# Noninvasive_Nexmeter.net
KiCad netlist of a schematic drawn in EAGLE
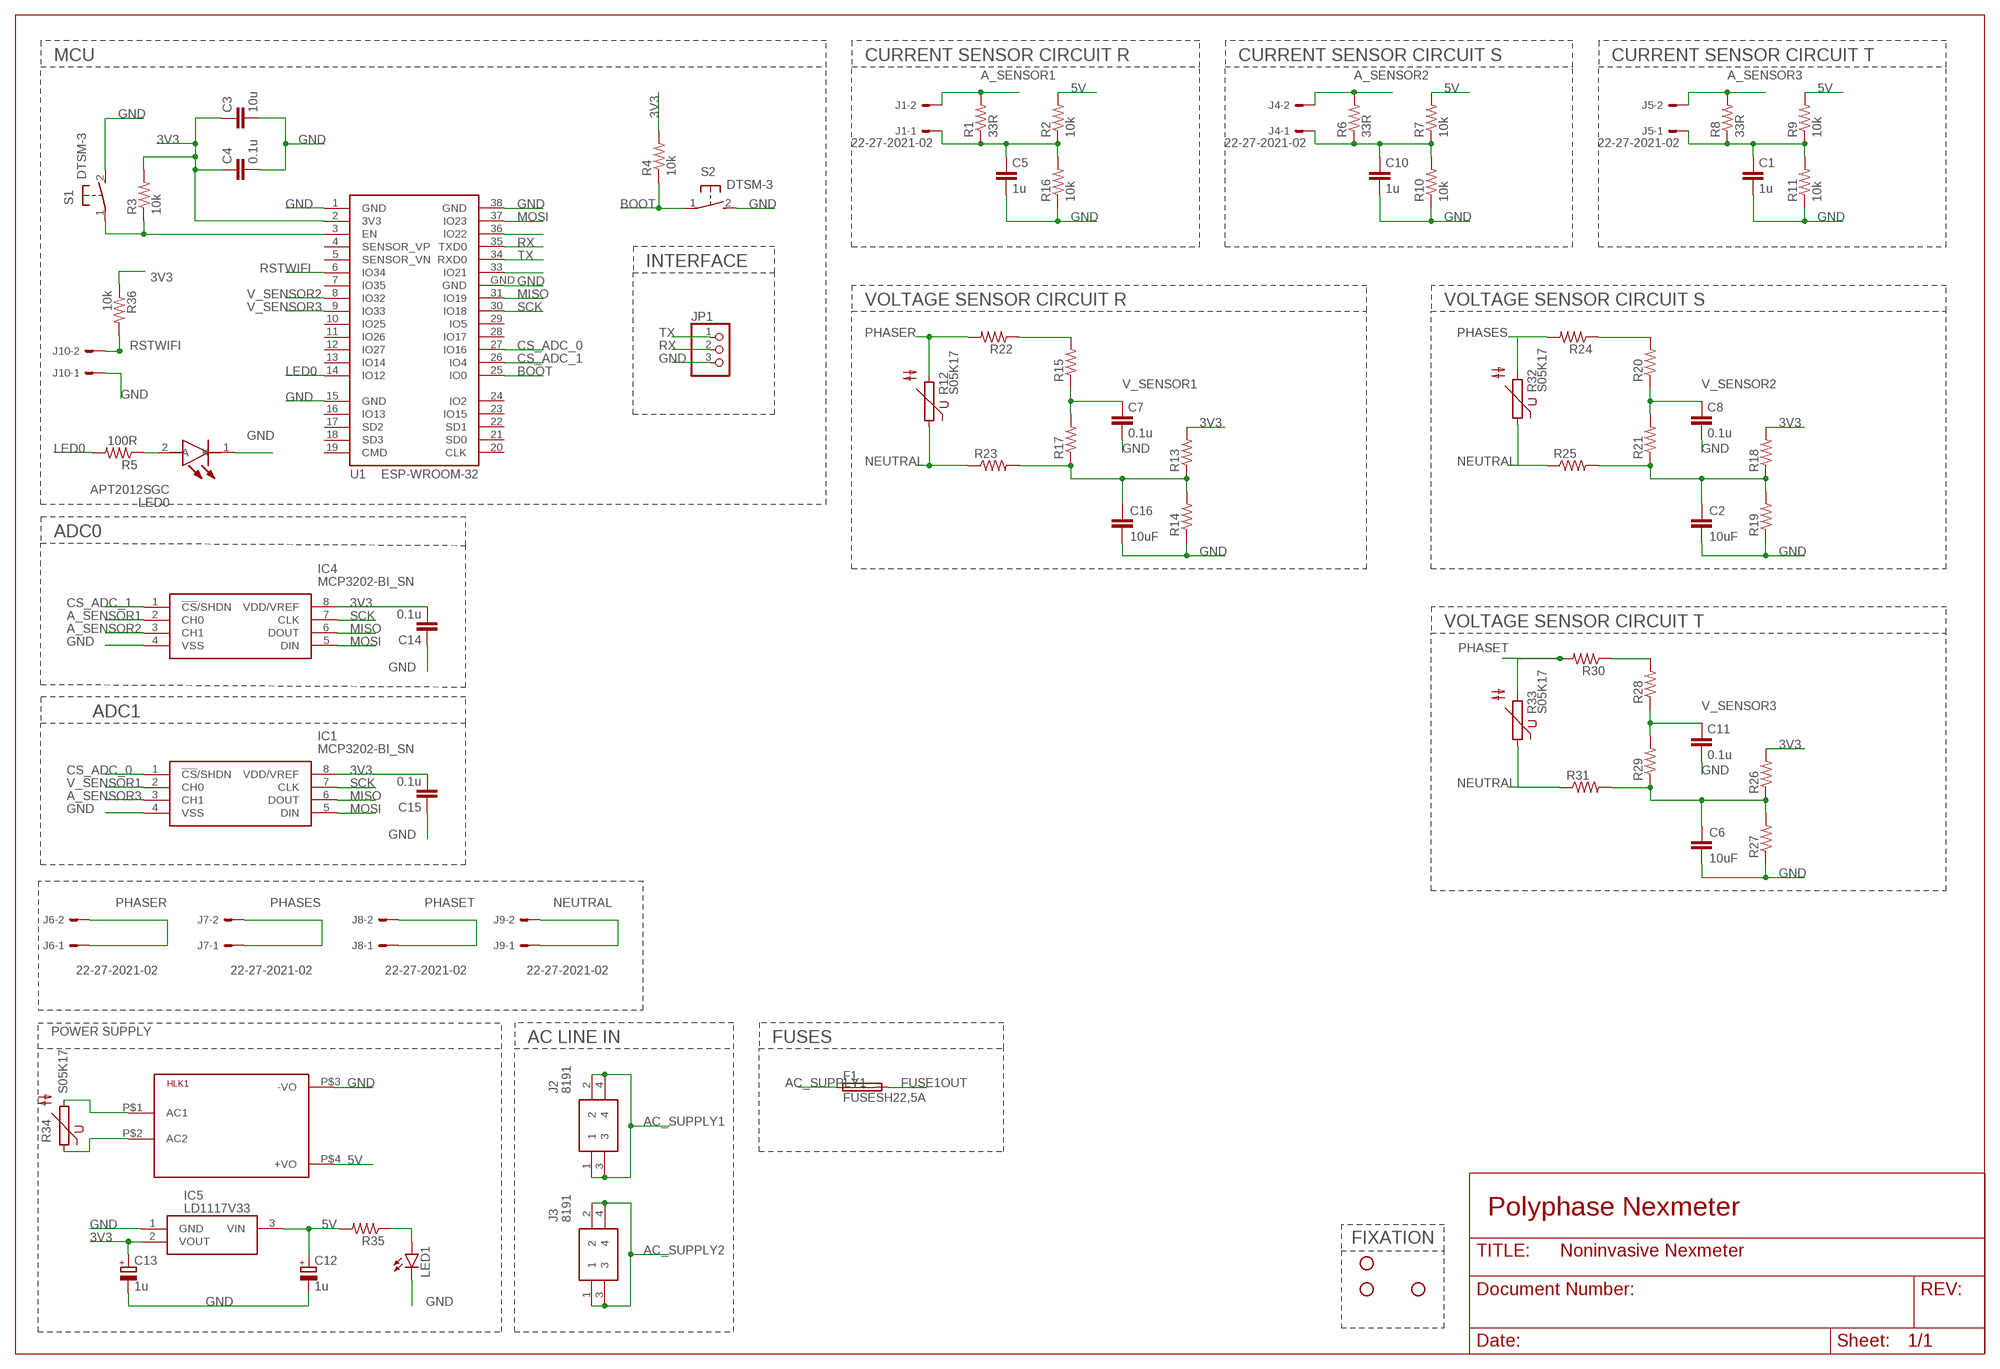
[diagram p0: schematic, sheet 1]

(export (version "E")
  (design (tool "Eeschema 10.0.6"))
  (components
    (comp (ref "C1")
      (value "1u")
      (footprint "eagle-import:C0805")
      (libsource (lib "eagle-import") (part "C-EUC0805"))
    )
    (comp (ref "C2")
      (value "10uF")
      (footprint "eagle-import:RCL_C0805")
      (libsource (lib "eagle-import") (part "RCL_C-EUC0805"))
    )
    (comp (ref "C3")
      (value "10u")
      (footprint "eagle-import:C0805")
      (libsource (lib "eagle-import") (part "C-EUC0805"))
    )
    (comp (ref "C4")
      (value "0.1u")
      (footprint "eagle-import:C0805")
      (libsource (lib "eagle-import") (part "C-EUC0805"))
    )
    (comp (ref "C5")
      (value "1u")
      (footprint "eagle-import:C0805")
      (libsource (lib "eagle-import") (part "C-EUC0805"))
    )
    (comp (ref "C6")
      (value "10uF")
      (footprint "eagle-import:RCL_C0805")
      (libsource (lib "eagle-import") (part "RCL_C-EUC0805"))
    )
    (comp (ref "C7")
      (value "0.1u")
      (footprint "eagle-import:C0805")
      (libsource (lib "eagle-import") (part "C-EUC0805"))
    )
    (comp (ref "C8")
      (value "0.1u")
      (footprint "eagle-import:C0805")
      (libsource (lib "eagle-import") (part "C-EUC0805"))
    )
    (comp (ref "C10")
      (value "1u")
      (footprint "eagle-import:C0805")
      (libsource (lib "eagle-import") (part "C-EUC0805"))
    )
    (comp (ref "C11")
      (value "0.1u")
      (footprint "eagle-import:C0805")
      (libsource (lib "eagle-import") (part "C-EUC0805"))
    )
    (comp (ref "C12")
      (value "1u")
      (footprint "eagle-import:E1,8-4")
      (libsource (lib "eagle-import") (part "CPOL-EUE1.8-4"))
    )
    (comp (ref "C13")
      (value "1u")
      (footprint "eagle-import:E1,8-4")
      (libsource (lib "eagle-import") (part "CPOL-EUE1.8-4"))
    )
    (comp (ref "C14")
      (value "0.1u")
      (footprint "eagle-import:C0805")
      (libsource (lib "eagle-import") (part "C-EUC0805"))
    )
    (comp (ref "C15")
      (value "0.1u")
      (footprint "eagle-import:C0805")
      (libsource (lib "eagle-import") (part "C-EUC0805"))
    )
    (comp (ref "C16")
      (value "10uF")
      (footprint "eagle-import:RCL_C0805")
      (libsource (lib "eagle-import") (part "RCL_C-EUC0805"))
    )
    (comp (ref "F1")
      (value "FUSESH22,5A")
      (footprint "eagle-import:SH22,5A")
      (libsource (lib "eagle-import") (part "FUSESH22,5A"))
    )
    (comp (ref "HLK1")
      (value "HLK-PM013W")
      (footprint "eagle-import:HLK-PM01")
      (libsource (lib "eagle-import") (part "HLK-PM013W"))
    )
    (comp (ref "IC1")
      (value "MCP3202-BI_SN")
      (footprint "eagle-import:SOIC127P600X175-8N")
      (fields
        (field (name "MANUFACTURER_PART_NUMBER") "MCP3202-BI/SN")
        (field (name "MOUSER_PART_NUMBER") "579-MCP3202BISN")
      )
      (libsource (lib "eagle-import") (part "MCP3202-BI_SN"))
    )
    (comp (ref "IC4")
      (value "MCP3202-BI_SN")
      (footprint "eagle-import:SOIC127P600X175-8N")
      (fields
        (field (name "MANUFACTURER_PART_NUMBER") "MCP3202-BI/SN")
        (field (name "MOUSER_PART_NUMBER") "579-MCP3202BISN")
      )
      (libsource (lib "eagle-import") (part "MCP3202-BI_SN"))
    )
    (comp (ref "IC5")
      (value "LD1117V33")
      (footprint "eagle-import:TO270P460X1020X2008-3P")
      (fields (field (name "MOUSER_PART_NUMBER") "511-LD1117V33"))
      (libsource (lib "eagle-import") (part "LD1117V33"))
    )
    (comp (ref "J1")
      (value "22-27-2021-02")
      (footprint "eagle-import:6410-02")
      (fields (field (name "MF") "MOLEX"))
      (libsource (lib "eagle-import") (part "22-?-0227-2021"))
    )
    (comp (ref "J2")
      (value "8191")
      (footprint "eagle-import:8191")
      (fields (field (name "MOUSER_PART_NUMBER") "534-8191"))
      (libsource (lib "eagle-import") (part "8191"))
    )
    (comp (ref "J3")
      (value "8191")
      (footprint "eagle-import:8191")
      (fields (field (name "MOUSER_PART_NUMBER") "534-8191"))
      (libsource (lib "eagle-import") (part "8191"))
    )
    (comp (ref "J4")
      (value "22-27-2021-02")
      (footprint "eagle-import:6410-02")
      (fields (field (name "MF") "MOLEX"))
      (libsource (lib "eagle-import") (part "22-?-0227-2021"))
    )
    (comp (ref "J5")
      (value "22-27-2021-02")
      (footprint "eagle-import:6410-02")
      (fields (field (name "MF") "MOLEX"))
      (libsource (lib "eagle-import") (part "22-?-0227-2021"))
    )
    (comp (ref "J6")
      (value "22-27-2021-02")
      (footprint "eagle-import:6410-02")
      (fields (field (name "MF") "MOLEX"))
      (libsource (lib "eagle-import") (part "22-?-0227-2021"))
    )
    (comp (ref "J7")
      (value "22-27-2021-02")
      (footprint "eagle-import:6410-02")
      (fields (field (name "MF") "MOLEX"))
      (libsource (lib "eagle-import") (part "22-?-0227-2021"))
    )
    (comp (ref "J8")
      (value "22-27-2021-02")
      (footprint "eagle-import:6410-02")
      (fields (field (name "MF") "MOLEX"))
      (libsource (lib "eagle-import") (part "22-?-0227-2021"))
    )
    (comp (ref "J9")
      (value "22-27-2021-02")
      (footprint "eagle-import:6410-02")
      (fields (field (name "MF") "MOLEX"))
      (libsource (lib "eagle-import") (part "22-?-0227-2021"))
    )
    (comp (ref "J10")
      (value "22-27-2021-02")
      (footprint "eagle-import:6410-02")
      (fields (field (name "MF") "MOLEX"))
      (libsource (lib "eagle-import") (part "22-?-0227-2021"))
    )
    (comp (ref "JP1")
      (value "PINHD-1X3")
      (footprint "eagle-import:1X03")
      (libsource (lib "eagle-import") (part "PINHD-1X3"))
    )
    (comp (ref "LED0")
      (value "APT2012SGC")
      (footprint "eagle-import:LEDC2012X85N")
      (fields (field (name "MOUSER_PART_NUMBER") "604-APT2012SGC"))
      (libsource (lib "eagle-import") (part "APT2012SGC"))
    )
    (comp (ref "LED1")
      (value "LED5MM")
      (footprint "eagle-import:LED5MM")
      (libsource (lib "eagle-import") (part "LED5MM"))
    )
    (comp (ref "R1")
      (value "33R")
      (footprint "eagle-import:R0805")
      (libsource (lib "eagle-import") (part "R-US_R0805"))
    )
    (comp (ref "R2")
      (value "10k")
      (footprint "eagle-import:R0805")
      (libsource (lib "eagle-import") (part "R-US_R0805"))
    )
    (comp (ref "R3")
      (value "10k")
      (footprint "eagle-import:R0805")
      (libsource (lib "eagle-import") (part "R-US_R0805"))
    )
    (comp (ref "R4")
      (value "10k")
      (footprint "eagle-import:R0805")
      (libsource (lib "eagle-import") (part "R-US_R0805"))
    )
    (comp (ref "R5")
      (value "100R")
      (footprint "eagle-import:R0805")
      (libsource (lib "eagle-import") (part "R-US_R0805"))
    )
    (comp (ref "R6")
      (value "33R")
      (footprint "eagle-import:R0805")
      (libsource (lib "eagle-import") (part "R-US_R0805"))
    )
    (comp (ref "R7")
      (value "10k")
      (footprint "eagle-import:R0805")
      (libsource (lib "eagle-import") (part "R-US_R0805"))
    )
    (comp (ref "R8")
      (value "33R")
      (footprint "eagle-import:R0805")
      (libsource (lib "eagle-import") (part "R-US_R0805"))
    )
    (comp (ref "R9")
      (value "10k")
      (footprint "eagle-import:R0805")
      (libsource (lib "eagle-import") (part "R-US_R0805"))
    )
    (comp (ref "R10")
      (value "10k")
      (footprint "eagle-import:R0805")
      (libsource (lib "eagle-import") (part "R-US_R0805"))
    )
    (comp (ref "R11")
      (value "10k")
      (footprint "eagle-import:R0805")
      (libsource (lib "eagle-import") (part "R-US_R0805"))
    )
    (comp (ref "R12")
      (value "S05K17")
      (footprint "eagle-import:S05K17")
      (libsource (lib "eagle-import") (part "S05K17"))
    )
    (comp (ref "R13")
      (value "RESISTOR0805")
      (footprint "eagle-import:0805")
      (libsource (lib "eagle-import") (part "RESISTOR0805"))
    )
    (comp (ref "R14")
      (value "RESISTOR0805")
      (footprint "eagle-import:0805")
      (libsource (lib "eagle-import") (part "RESISTOR0805"))
    )
    (comp (ref "R15")
      (value "RESISTOR0805")
      (footprint "eagle-import:0805")
      (libsource (lib "eagle-import") (part "RESISTOR0805"))
    )
    (comp (ref "R16")
      (value "10k")
      (footprint "eagle-import:R0805")
      (libsource (lib "eagle-import") (part "R-US_R0805"))
    )
    (comp (ref "R17")
      (value "RESISTOR0805")
      (footprint "eagle-import:0805")
      (libsource (lib "eagle-import") (part "RESISTOR0805"))
    )
    (comp (ref "R18")
      (value "RESISTOR0805")
      (footprint "eagle-import:0805")
      (libsource (lib "eagle-import") (part "RESISTOR0805"))
    )
    (comp (ref "R19")
      (value "RESISTOR0805")
      (footprint "eagle-import:0805")
      (libsource (lib "eagle-import") (part "RESISTOR0805"))
    )
    (comp (ref "R20")
      (value "RESISTOR0805")
      (footprint "eagle-import:0805")
      (libsource (lib "eagle-import") (part "RESISTOR0805"))
    )
    (comp (ref "R21")
      (value "RESISTOR0805")
      (footprint "eagle-import:0805")
      (libsource (lib "eagle-import") (part "RESISTOR0805"))
    )
    (comp (ref "R22")
      (value "RESISTOR0805")
      (footprint "eagle-import:0805")
      (libsource (lib "eagle-import") (part "RESISTOR0805"))
    )
    (comp (ref "R23")
      (value "RESISTOR0805")
      (footprint "eagle-import:0805")
      (libsource (lib "eagle-import") (part "RESISTOR0805"))
    )
    (comp (ref "R24")
      (value "RESISTOR0805")
      (footprint "eagle-import:0805")
      (libsource (lib "eagle-import") (part "RESISTOR0805"))
    )
    (comp (ref "R25")
      (value "RESISTOR0805")
      (footprint "eagle-import:0805")
      (libsource (lib "eagle-import") (part "RESISTOR0805"))
    )
    (comp (ref "R26")
      (value "RESISTOR0805")
      (footprint "eagle-import:0805")
      (libsource (lib "eagle-import") (part "RESISTOR0805"))
    )
    (comp (ref "R27")
      (value "RESISTOR0805")
      (footprint "eagle-import:0805")
      (libsource (lib "eagle-import") (part "RESISTOR0805"))
    )
    (comp (ref "R28")
      (value "RESISTOR0805")
      (footprint "eagle-import:0805")
      (libsource (lib "eagle-import") (part "RESISTOR0805"))
    )
    (comp (ref "R29")
      (value "RESISTOR0805")
      (footprint "eagle-import:0805")
      (libsource (lib "eagle-import") (part "RESISTOR0805"))
    )
    (comp (ref "R30")
      (value "RESISTOR0805")
      (footprint "eagle-import:0805")
      (libsource (lib "eagle-import") (part "RESISTOR0805"))
    )
    (comp (ref "R31")
      (value "RESISTOR0805")
      (footprint "eagle-import:0805")
      (libsource (lib "eagle-import") (part "RESISTOR0805"))
    )
    (comp (ref "R32")
      (value "S05K17")
      (footprint "eagle-import:S05K17")
      (libsource (lib "eagle-import") (part "S05K17"))
    )
    (comp (ref "R33")
      (value "S05K17")
      (footprint "eagle-import:S05K17")
      (libsource (lib "eagle-import") (part "S05K17"))
    )
    (comp (ref "R34")
      (value "S05K17")
      (footprint "eagle-import:S05K17")
      (libsource (lib "eagle-import") (part "S05K17"))
    )
    (comp (ref "R35")
      (value "RESISTOR0805")
      (footprint "eagle-import:0805")
      (libsource (lib "eagle-import") (part "RESISTOR0805"))
    )
    (comp (ref "R36")
      (value "10k")
      (footprint "eagle-import:R0805")
      (libsource (lib "eagle-import") (part "R-US_R0805"))
    )
    (comp (ref "S1")
      (value "DTSM-3")
      (footprint "eagle-import:DTSM-3")
      (libsource (lib "eagle-import") (part "DTSM-3"))
    )
    (comp (ref "S2")
      (value "DTSM-3")
      (footprint "eagle-import:DTSM-3")
      (libsource (lib "eagle-import") (part "DTSM-3"))
    )
    (comp (ref "STANDOFF1")
      (value "STAND-OFF")
      (footprint "eagle-import:STAND-OFF")
      (libsource (lib "eagle-import") (part "STAND-OFF"))
    )
    (comp (ref "STANDOFF2")
      (value "STAND-OFF")
      (footprint "eagle-import:STAND-OFF")
      (libsource (lib "eagle-import") (part "STAND-OFF"))
    )
    (comp (ref "STANDOFF4")
      (value "STAND-OFF")
      (footprint "eagle-import:STAND-OFF")
      (libsource (lib "eagle-import") (part "STAND-OFF"))
    )
    (comp (ref "U1")
      (value "ESP-WROOM-32")
      (footprint "eagle-import:ESP-WROOM-32")
      (libsource (lib "eagle-import") (part "ESP-WROOM-32"))
    )
  )
  (nets
    (net (code "1") (name "/3V3") (class "Default")
      (node (ref "C13") (pin "+") (pinfunction "+_+") (pintype "passive"))
      (node (ref "C14") (pin "2") (pinfunction "2_2") (pintype "passive"))
      (node (ref "C15") (pin "2") (pinfunction "2_2") (pintype "passive"))
      (node (ref "C3") (pin "1") (pinfunction "1_1") (pintype "passive"))
      (node (ref "C4") (pin "1") (pinfunction "1_1") (pintype "passive"))
      (node (ref "IC1") (pin "8") (pinfunction "VDD/VREF_8") (pintype "power_in"))
      (node (ref "IC4") (pin "8") (pinfunction "VDD/VREF_8") (pintype "power_in"))
      (node (ref "IC5") (pin "2") (pinfunction "VOUT_2") (pintype "output"))
      (node (ref "R13") (pin "2") (pinfunction "2_2") (pintype "passive"))
      (node (ref "R18") (pin "2") (pinfunction "2_2") (pintype "passive"))
      (node (ref "R26") (pin "2") (pinfunction "2_2") (pintype "passive"))
      (node (ref "R3") (pin "2") (pinfunction "2_2") (pintype "passive"))
      (node (ref "R36") (pin "1") (pinfunction "1_1") (pintype "passive"))
      (node (ref "R4") (pin "2") (pinfunction "2_2") (pintype "passive"))
      (node (ref "U1") (pin "2") (pinfunction "3V3_2") (pintype "power_in"))
    )
    (net (code "2") (name "/5V") (class "Default")
      (node (ref "C12") (pin "+") (pinfunction "+_+") (pintype "passive"))
      (node (ref "HLK1") (pin "P$4") (pinfunction "+VO_P$4") (pintype "bidirectional"))
      (node (ref "IC5") (pin "3") (pinfunction "VIN_3") (pintype "input"))
      (node (ref "R2") (pin "2") (pinfunction "2_2") (pintype "passive"))
      (node (ref "R35") (pin "2") (pinfunction "2_2") (pintype "passive"))
      (node (ref "R7") (pin "2") (pinfunction "2_2") (pintype "passive"))
      (node (ref "R9") (pin "2") (pinfunction "2_2") (pintype "passive"))
    )
    (net (code "3") (name "/AC_SUPPLY1") (class "Default")
      (node (ref "F1") (pin "1") (pinfunction "1_1") (pintype "passive"))
      (node (ref "J2") (pin "1") (pinfunction "1_1") (pintype "bidirectional"))
      (node (ref "J2") (pin "2") (pinfunction "2_2") (pintype "bidirectional"))
      (node (ref "J2") (pin "3") (pinfunction "3_3") (pintype "bidirectional"))
      (node (ref "J2") (pin "4") (pinfunction "4_4") (pintype "bidirectional"))
    )
    (net (code "4") (name "/AC_SUPPLY2") (class "Default")
      (node (ref "HLK1") (pin "P$2") (pinfunction "AC2_P$2") (pintype "bidirectional"))
      (node (ref "J3") (pin "1") (pinfunction "1_1") (pintype "bidirectional"))
      (node (ref "J3") (pin "2") (pinfunction "2_2") (pintype "bidirectional"))
      (node (ref "J3") (pin "3") (pinfunction "3_3") (pintype "bidirectional"))
      (node (ref "J3") (pin "4") (pinfunction "4_4") (pintype "bidirectional"))
      (node (ref "R34") (pin "1") (pinfunction "1_1") (pintype "passive"))
    )
    (net (code "5") (name "/A_SENSOR1") (class "Default")
      (node (ref "IC4") (pin "2") (pinfunction "CH0_2") (pintype "bidirectional"))
      (node (ref "J1") (pin "2") (pinfunction "S_2") (pintype "passive"))
      (node (ref "R1") (pin "2") (pinfunction "2_2") (pintype "passive"))
    )
    (net (code "6") (name "/A_SENSOR2") (class "Default")
      (node (ref "IC4") (pin "3") (pinfunction "CH1_3") (pintype "bidirectional"))
      (node (ref "J4") (pin "2") (pinfunction "S_2") (pintype "passive"))
      (node (ref "R6") (pin "2") (pinfunction "2_2") (pintype "passive"))
    )
    (net (code "7") (name "/A_SENSOR3") (class "Default")
      (node (ref "IC1") (pin "3") (pinfunction "CH1_3") (pintype "bidirectional"))
      (node (ref "J5") (pin "2") (pinfunction "S_2") (pintype "passive"))
      (node (ref "R8") (pin "2") (pinfunction "2_2") (pintype "passive"))
    )
    (net (code "8") (name "/BOOT") (class "Default")
      (node (ref "R4") (pin "1") (pinfunction "1_1") (pintype "passive"))
      (node (ref "S2") (pin "1") (pinfunction "1_1") (pintype "passive"))
      (node (ref "U1") (pin "25") (pinfunction "IO0_25") (pintype "bidirectional"))
    )
    (net (code "9") (name "/CS_ADC_0") (class "Default")
      (node (ref "IC1") (pin "1") (pinfunction "~{CS}/SHDN_1") (pintype "input"))
      (node (ref "U1") (pin "27") (pinfunction "IO16_27") (pintype "bidirectional"))
    )
    (net (code "10") (name "/CS_ADC_1") (class "Default")
      (node (ref "IC4") (pin "1") (pinfunction "~{CS}/SHDN_1") (pintype "input"))
      (node (ref "U1") (pin "26") (pinfunction "IO4_26") (pintype "bidirectional"))
    )
    (net (code "11") (name "/FUSE1OUT") (class "Default")
      (node (ref "F1") (pin "2") (pinfunction "2_2") (pintype "passive"))
      (node (ref "HLK1") (pin "P$1") (pinfunction "AC1_P$1") (pintype "bidirectional"))
      (node (ref "R34") (pin "2") (pinfunction "2_2") (pintype "passive"))
    )
    (net (code "12") (name "/GND") (class "Default")
      (node (ref "C1") (pin "2") (pinfunction "2_2") (pintype "passive"))
      (node (ref "C10") (pin "2") (pinfunction "2_2") (pintype "passive"))
      (node (ref "C11") (pin "2") (pinfunction "2_2") (pintype "passive"))
      (node (ref "C12") (pin "-") (pinfunction "-_-") (pintype "passive"))
      (node (ref "C13") (pin "-") (pinfunction "-_-") (pintype "passive"))
      (node (ref "C14") (pin "1") (pinfunction "1_1") (pintype "passive"))
      (node (ref "C15") (pin "1") (pinfunction "1_1") (pintype "passive"))
      (node (ref "C16") (pin "2") (pinfunction "2_2") (pintype "passive"))
      (node (ref "C2") (pin "2") (pinfunction "2_2") (pintype "passive"))
      (node (ref "C3") (pin "2") (pinfunction "2_2") (pintype "passive"))
      (node (ref "C4") (pin "2") (pinfunction "2_2") (pintype "passive"))
      (node (ref "C5") (pin "2") (pinfunction "2_2") (pintype "passive"))
      (node (ref "C6") (pin "2") (pinfunction "2_2") (pintype "passive"))
      (node (ref "C7") (pin "2") (pinfunction "2_2") (pintype "passive"))
      (node (ref "C8") (pin "2") (pinfunction "2_2") (pintype "passive"))
      (node (ref "HLK1") (pin "P$3") (pinfunction "-VO_P$3") (pintype "bidirectional"))
      (node (ref "IC1") (pin "4") (pinfunction "VSS_4") (pintype "power_in"))
      (node (ref "IC4") (pin "4") (pinfunction "VSS_4") (pintype "power_in"))
      (node (ref "IC5") (pin "1") (pinfunction "GND_1") (pintype "power_in"))
      (node (ref "J10") (pin "1") (pinfunction "S_1") (pintype "passive"))
      (node (ref "JP1") (pin "3") (pinfunction "3_3") (pintype "passive"))
      (node (ref "LED0") (pin "1") (pinfunction "K_1") (pintype "bidirectional"))
      (node (ref "LED1") (pin "K") (pinfunction "C_K") (pintype "passive"))
      (node (ref "R10") (pin "1") (pinfunction "1_1") (pintype "passive"))
      (node (ref "R11") (pin "1") (pinfunction "1_1") (pintype "passive"))
      (node (ref "R14") (pin "1") (pinfunction "1_1") (pintype "passive"))
      (node (ref "R16") (pin "1") (pinfunction "1_1") (pintype "passive"))
      (node (ref "R19") (pin "1") (pinfunction "1_1") (pintype "passive"))
      (node (ref "R27") (pin "1") (pinfunction "1_1") (pintype "passive"))
      (node (ref "S1") (pin "2") (pinfunction "2_2") (pintype "passive"))
      (node (ref "S2") (pin "2") (pinfunction "2_2") (pintype "passive"))
      (node (ref "U1") (pin "1") (pinfunction "GND_1") (pintype "power_in"))
      (node (ref "U1") (pin "15") (pinfunction "GND_15") (pintype "power_in"))
      (node (ref "U1") (pin "38") (pinfunction "GND_38") (pintype "power_in"))
      (node (ref "U1") (pin "GND") (pinfunction "GND_GND") (pintype "power_in"))
    )
    (net (code "13") (name "/LED0") (class "Default")
      (node (ref "R5") (pin "2") (pinfunction "2_2") (pintype "passive"))
      (node (ref "U1") (pin "14") (pinfunction "IO12_14") (pintype "bidirectional"))
    )
    (net (code "14") (name "/MISO") (class "Default")
      (node (ref "IC1") (pin "6") (pinfunction "DOUT_6") (pintype "output"))
      (node (ref "IC4") (pin "6") (pinfunction "DOUT_6") (pintype "output"))
      (node (ref "U1") (pin "31") (pinfunction "IO19_31") (pintype "bidirectional"))
    )
    (net (code "15") (name "/MOSI") (class "Default")
      (node (ref "IC1") (pin "5") (pinfunction "DIN_5") (pintype "input"))
      (node (ref "IC4") (pin "5") (pinfunction "DIN_5") (pintype "input"))
      (node (ref "U1") (pin "37") (pinfunction "IO23_37") (pintype "bidirectional"))
    )
    (net (code "16") (name "/NEUTRAL") (class "Default")
      (node (ref "J9") (pin "1") (pinfunction "S_1") (pintype "passive"))
      (node (ref "J9") (pin "2") (pinfunction "S_2") (pintype "passive"))
      (node (ref "R12") (pin "1") (pinfunction "1_1") (pintype "passive"))
      (node (ref "R23") (pin "1") (pinfunction "1_1") (pintype "passive"))
      (node (ref "R25") (pin "1") (pinfunction "1_1") (pintype "passive"))
      (node (ref "R31") (pin "1") (pinfunction "1_1") (pintype "passive"))
      (node (ref "R32") (pin "1") (pinfunction "1_1") (pintype "passive"))
      (node (ref "R33") (pin "1") (pinfunction "1_1") (pintype "passive"))
    )
    (net (code "17") (name "/PHASER") (class "Default")
      (node (ref "J6") (pin "1") (pinfunction "S_1") (pintype "passive"))
      (node (ref "J6") (pin "2") (pinfunction "S_2") (pintype "passive"))
      (node (ref "R12") (pin "2") (pinfunction "2_2") (pintype "passive"))
      (node (ref "R22") (pin "2") (pinfunction "2_2") (pintype "passive"))
    )
    (net (code "18") (name "/PHASES") (class "Default")
      (node (ref "J7") (pin "1") (pinfunction "S_1") (pintype "passive"))
      (node (ref "J7") (pin "2") (pinfunction "S_2") (pintype "passive"))
      (node (ref "R24") (pin "2") (pinfunction "2_2") (pintype "passive"))
      (node (ref "R32") (pin "2") (pinfunction "2_2") (pintype "passive"))
    )
    (net (code "19") (name "/PHASET") (class "Default")
      (node (ref "J8") (pin "1") (pinfunction "S_1") (pintype "passive"))
      (node (ref "J8") (pin "2") (pinfunction "S_2") (pintype "passive"))
      (node (ref "R30") (pin "2") (pinfunction "2_2") (pintype "passive"))
      (node (ref "R33") (pin "2") (pinfunction "2_2") (pintype "passive"))
    )
    (net (code "20") (name "/RSTWIFI") (class "Default")
      (node (ref "J10") (pin "2") (pinfunction "S_2") (pintype "passive"))
      (node (ref "R36") (pin "2") (pinfunction "2_2") (pintype "passive"))
      (node (ref "U1") (pin "6") (pinfunction "IO34_6") (pintype "bidirectional"))
    )
    (net (code "21") (name "/RX") (class "Default")
      (node (ref "JP1") (pin "2") (pinfunction "2_2") (pintype "passive"))
      (node (ref "U1") (pin "35") (pinfunction "TXD0_35") (pintype "bidirectional"))
    )
    (net (code "22") (name "/SCK") (class "Default")
      (node (ref "IC1") (pin "7") (pinfunction "CLK_7") (pintype "input"))
      (node (ref "IC4") (pin "7") (pinfunction "CLK_7") (pintype "input"))
      (node (ref "U1") (pin "30") (pinfunction "IO18_30") (pintype "bidirectional"))
    )
    (net (code "23") (name "/TX") (class "Default")
      (node (ref "JP1") (pin "1") (pinfunction "1_1") (pintype "passive"))
      (node (ref "U1") (pin "34") (pinfunction "RXD0_34") (pintype "bidirectional"))
    )
    (net (code "24") (name "/V_SENSOR1") (class "Default")
      (node (ref "C7") (pin "1") (pinfunction "1_1") (pintype "passive"))
      (node (ref "IC1") (pin "2") (pinfunction "CH0_2") (pintype "bidirectional"))
      (node (ref "R15") (pin "1") (pinfunction "1_1") (pintype "passive"))
      (node (ref "R17") (pin "2") (pinfunction "2_2") (pintype "passive"))
    )
    (net (code "25") (name "/V_SENSOR2") (class "Default")
      (node (ref "C8") (pin "1") (pinfunction "1_1") (pintype "passive"))
      (node (ref "R20") (pin "1") (pinfunction "1_1") (pintype "passive"))
      (node (ref "R21") (pin "2") (pinfunction "2_2") (pintype "passive"))
      (node (ref "U1") (pin "8") (pinfunction "IO32_8") (pintype "bidirectional"))
    )
    (net (code "26") (name "/V_SENSOR3") (class "Default")
      (node (ref "C11") (pin "1") (pinfunction "1_1") (pintype "passive"))
      (node (ref "R28") (pin "1") (pinfunction "1_1") (pintype "passive"))
      (node (ref "R29") (pin "2") (pinfunction "2_2") (pintype "passive"))
      (node (ref "U1") (pin "9") (pinfunction "IO33_9") (pintype "bidirectional"))
    )
    (net (code "27") (name "Net-(C2-Pad1)") (class "Default")
      (node (ref "C2") (pin "1") (pinfunction "1_1") (pintype "passive"))
      (node (ref "R18") (pin "1") (pinfunction "1_1") (pintype "passive"))
      (node (ref "R19") (pin "2") (pinfunction "2_2") (pintype "passive"))
      (node (ref "R21") (pin "1") (pinfunction "1_1") (pintype "passive"))
      (node (ref "R25") (pin "2") (pinfunction "2_2") (pintype "passive"))
    )
    (net (code "28") (name "Net-(C6-Pad1)") (class "Default")
      (node (ref "C6") (pin "1") (pinfunction "1_1") (pintype "passive"))
      (node (ref "R26") (pin "1") (pinfunction "1_1") (pintype "passive"))
      (node (ref "R27") (pin "2") (pinfunction "2_2") (pintype "passive"))
      (node (ref "R29") (pin "1") (pinfunction "1_1") (pintype "passive"))
      (node (ref "R31") (pin "2") (pinfunction "2_2") (pintype "passive"))
    )
    (net (code "29") (name "Net-(C16-Pad1)") (class "Default")
      (node (ref "C16") (pin "1") (pinfunction "1_1") (pintype "passive"))
      (node (ref "R13") (pin "1") (pinfunction "1_1") (pintype "passive"))
      (node (ref "R14") (pin "2") (pinfunction "2_2") (pintype "passive"))
      (node (ref "R17") (pin "1") (pinfunction "1_1") (pintype "passive"))
      (node (ref "R23") (pin "2") (pinfunction "2_2") (pintype "passive"))
    )
    (net (code "30") (name "Net-(J1A-S)") (class "Default")
      (node (ref "C5") (pin "1") (pinfunction "1_1") (pintype "passive"))
      (node (ref "J1") (pin "1") (pinfunction "S_1") (pintype "passive"))
      (node (ref "R1") (pin "1") (pinfunction "1_1") (pintype "passive"))
      (node (ref "R16") (pin "2") (pinfunction "2_2") (pintype "passive"))
      (node (ref "R2") (pin "1") (pinfunction "1_1") (pintype "passive"))
    )
    (net (code "31") (name "Net-(J4A-S)") (class "Default")
      (node (ref "C10") (pin "1") (pinfunction "1_1") (pintype "passive"))
      (node (ref "J4") (pin "1") (pinfunction "S_1") (pintype "passive"))
      (node (ref "R10") (pin "2") (pinfunction "2_2") (pintype "passive"))
      (node (ref "R6") (pin "1") (pinfunction "1_1") (pintype "passive"))
      (node (ref "R7") (pin "1") (pinfunction "1_1") (pintype "passive"))
    )
    (net (code "32") (name "Net-(J5A-S)") (class "Default")
      (node (ref "C1") (pin "1") (pinfunction "1_1") (pintype "passive"))
      (node (ref "J5") (pin "1") (pinfunction "S_1") (pintype "passive"))
      (node (ref "R11") (pin "2") (pinfunction "2_2") (pintype "passive"))
      (node (ref "R8") (pin "1") (pinfunction "1_1") (pintype "passive"))
      (node (ref "R9") (pin "1") (pinfunction "1_1") (pintype "passive"))
    )
    (net (code "33") (name "Net-(LED0-A)") (class "Default")
      (node (ref "LED0") (pin "2") (pinfunction "A_2") (pintype "bidirectional"))
      (node (ref "R5") (pin "1") (pinfunction "1_1") (pintype "passive"))
    )
    (net (code "34") (name "Net-(LED1-PadA)") (class "Default")
      (node (ref "LED1") (pin "A") (pinfunction "A_A") (pintype "passive"))
      (node (ref "R35") (pin "1") (pinfunction "1_1") (pintype "passive"))
    )
    (net (code "35") (name "Net-(R15-Pad2)") (class "Default")
      (node (ref "R15") (pin "2") (pinfunction "2_2") (pintype "passive"))
      (node (ref "R22") (pin "1") (pinfunction "1_1") (pintype "passive"))
    )
    (net (code "36") (name "Net-(R20-Pad2)") (class "Default")
      (node (ref "R20") (pin "2") (pinfunction "2_2") (pintype "passive"))
      (node (ref "R24") (pin "1") (pinfunction "1_1") (pintype "passive"))
    )
    (net (code "37") (name "Net-(R28-Pad2)") (class "Default")
      (node (ref "R28") (pin "2") (pinfunction "2_2") (pintype "passive"))
      (node (ref "R30") (pin "1") (pinfunction "1_1") (pintype "passive"))
    )
    (net (code "38") (name "Net-(U1-EN)") (class "Default")
      (node (ref "R3") (pin "1") (pinfunction "1_1") (pintype "passive"))
      (node (ref "S1") (pin "1") (pinfunction "1_1") (pintype "passive"))
      (node (ref "U1") (pin "3") (pinfunction "EN_3") (pintype "input"))
    )
    (net (code "39") (name "unconnected-(U1-CLK-Pad20)") (class "Default")
      (node (ref "U1") (pin "20") (pinfunction "CLK_20") (pintype "bidirectional"))
    )
    (net (code "40") (name "unconnected-(U1-CMD-Pad19)") (class "Default")
      (node (ref "U1") (pin "19") (pinfunction "CMD_19") (pintype "bidirectional"))
    )
    (net (code "41") (name "unconnected-(U1-IO2-Pad24)") (class "Default")
      (node (ref "U1") (pin "24") (pinfunction "IO2_24") (pintype "bidirectional"))
    )
    (net (code "42") (name "unconnected-(U1-IO5-Pad29)") (class "Default")
      (node (ref "U1") (pin "29") (pinfunction "IO5_29") (pintype "bidirectional"))
    )
    (net (code "43") (name "unconnected-(U1-IO13-Pad16)") (class "Default")
      (node (ref "U1") (pin "16") (pinfunction "IO13_16") (pintype "bidirectional"))
    )
    (net (code "44") (name "unconnected-(U1-IO14-Pad13)") (class "Default")
      (node (ref "U1") (pin "13") (pinfunction "IO14_13") (pintype "bidirectional"))
    )
    (net (code "45") (name "unconnected-(U1-IO15-Pad23)") (class "Default")
      (node (ref "U1") (pin "23") (pinfunction "IO15_23") (pintype "bidirectional"))
    )
    (net (code "46") (name "unconnected-(U1-IO17-Pad28)") (class "Default")
      (node (ref "U1") (pin "28") (pinfunction "IO17_28") (pintype "bidirectional"))
    )
    (net (code "47") (name "unconnected-(U1-IO21-Pad33)") (class "Default")
      (node (ref "U1") (pin "33") (pinfunction "IO21_33") (pintype "bidirectional"))
    )
    (net (code "48") (name "unconnected-(U1-IO22-Pad36)") (class "Default")
      (node (ref "U1") (pin "36") (pinfunction "IO22_36") (pintype "bidirectional"))
    )
    (net (code "49") (name "unconnected-(U1-IO25-Pad10)") (class "Default")
      (node (ref "U1") (pin "10") (pinfunction "IO25_10") (pintype "bidirectional"))
    )
    (net (code "50") (name "unconnected-(U1-IO26-Pad11)") (class "Default")
      (node (ref "U1") (pin "11") (pinfunction "IO26_11") (pintype "bidirectional"))
    )
    (net (code "51") (name "unconnected-(U1-IO27-Pad12)") (class "Default")
      (node (ref "U1") (pin "12") (pinfunction "IO27_12") (pintype "bidirectional"))
    )
    (net (code "52") (name "unconnected-(U1-IO35-Pad7)") (class "Default")
      (node (ref "U1") (pin "7") (pinfunction "IO35_7") (pintype "bidirectional"))
    )
    (net (code "53") (name "unconnected-(U1-SD0-Pad21)") (class "Default")
      (node (ref "U1") (pin "21") (pinfunction "SD0_21") (pintype "bidirectional"))
    )
    (net (code "54") (name "unconnected-(U1-SD1-Pad22)") (class "Default")
      (node (ref "U1") (pin "22") (pinfunction "SD1_22") (pintype "bidirectional"))
    )
    (net (code "55") (name "unconnected-(U1-SD2-Pad17)") (class "Default")
      (node (ref "U1") (pin "17") (pinfunction "SD2_17") (pintype "bidirectional"))
    )
    (net (code "56") (name "unconnected-(U1-SD3-Pad18)") (class "Default")
      (node (ref "U1") (pin "18") (pinfunction "SD3_18") (pintype "bidirectional"))
    )
    (net (code "57") (name "unconnected-(U1-SENSOR_VN-Pad5)") (class "Default")
      (node (ref "U1") (pin "5") (pinfunction "SENSOR_VN_5") (pintype "bidirectional"))
    )
    (net (code "58") (name "unconnected-(U1-SENSOR_VP-Pad4)") (class "Default")
      (node (ref "U1") (pin "4") (pinfunction "SENSOR_VP_4") (pintype "bidirectional"))
    )
  )
)
